# 01_ESP-CAM.net
KiCad netlist of a schematic drawn in Altium Designer
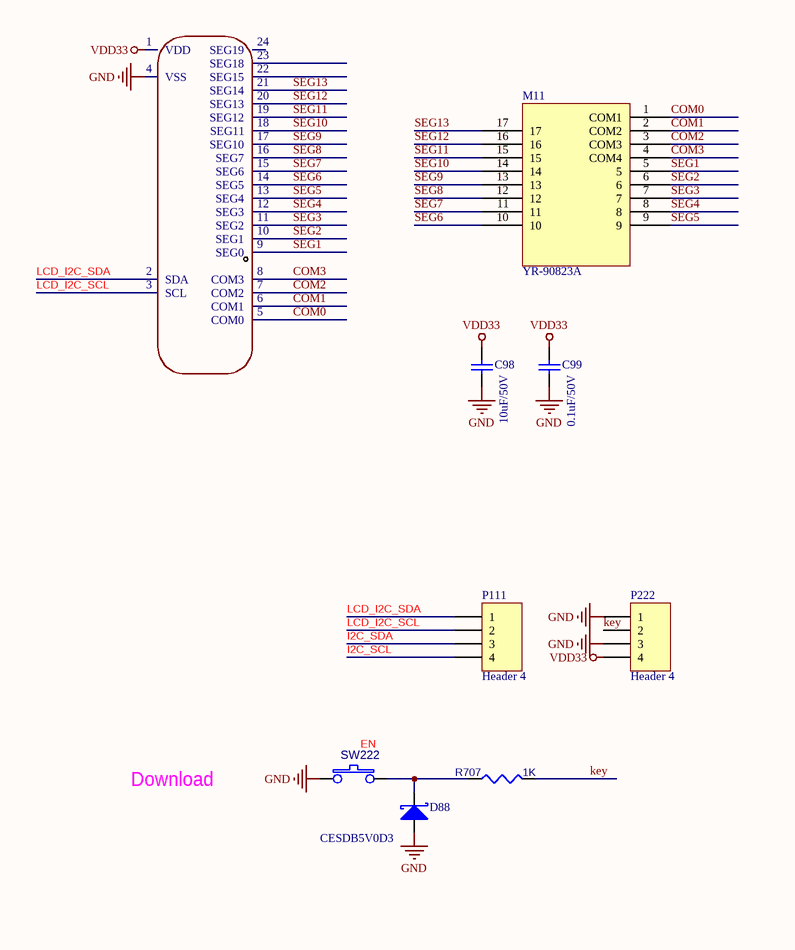
[diagram p0: 01_ESP-CAM.SchDoc, top left]
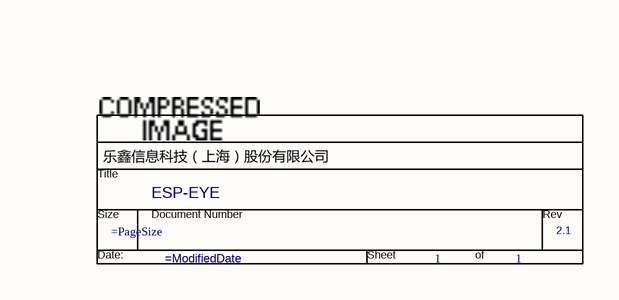
[diagram p1: 01_ESP-CAM.SchDoc, bottom right]

(export (version "E")
  (design (tool "Eeschema 10.0.6"))
  (components
    (comp (ref "*")
      (value "~")
      (fields
        (field (name "REVCODE") "2.1")
        (field (name "TITLE") "ESP-EYE")
        (field (name "PAGE NUMBER") "1")
        (field (name "PAGE COUNT") "1")
      )
      (libsource (lib "*") (part "espTitleBlock1"))
    )
    (comp (ref "C98")
      (value "10uF/50V")
      (footprint "0805C")
      (description "Capacitor")
      (fields (field (name "PUBLISHER") "Altium Limited"))
      (libsource (lib "Miscellaneous Devices") (part "Cap"))
    )
    (comp (ref "C99")
      (value "0.1uF/50V")
      (footprint "0603C")
      (description "Capacitor")
      (fields (field (name "PUBLISHER") "Altium Limited"))
      (libsource (lib "Miscellaneous Devices") (part "Cap"))
    )
    (comp (ref "D88")
      (value "CESDB5V0D3")
      (footprint "SOD323")
      (description "Schottky Diode")
      (libsource (lib "*") (part "DIODE S"))
    )
    (comp (ref "M11")
      (value "YR-90823A")
      (footprint "YR-90823A")
      (libsource (lib "Schlib_20110825") (part "YR-90823A"))
    )
    (comp (ref "P111")
      (value "Header 4")
      (footprint "1.27-4P")
      (description "Header, 4-Pin")
      (fields (field (name "PUBLISHER") "Altium Limited"))
      (libsource (lib "Miscellaneous Connectors") (part "Header 4"))
    )
    (comp (ref "P222")
      (value "Header 4")
      (footprint "1.27-4P")
      (description "Header, 4-Pin")
      (fields (field (name "PUBLISHER") "Altium Limited"))
      (libsource (lib "Miscellaneous Connectors") (part "Header 4"))
    )
    (comp (ref "R707")
      (value "1K")
      (footprint "0402R")
      (fields (field (name "Comment") "RESISTOR_0"))
      (libsource (lib "*") (part "RESISTOR_0"))
    )
    (comp (ref "SW222")
      (value "SW PUSHBUTTON")
      (footprint "SW-SMD_L3.9-W3.0-P4.45")
      (libsource (lib "*") (part "SW PUSHBUTTON"))
    )
    (comp (ref "U222")
      (value "HT16C21A-24SOP")
      (footprint "SOP65P640X265-24N")
      (fields (field (name "MANUFACTURER PART") "HT1621BM/TR"))
      (libsource (lib "Schlib_20110825") (part "HT16C21A-24SOP"))
    )
  )
  (nets
    (net (code "1") (name "/COM0") (class "Default")
      (node (ref "M11") (pin "1") (pinfunction "COM1_1") (pintype "passive"))
      (node (ref "U222") (pin "5") (pinfunction "COM0_5") (pintype "passive"))
    )
    (net (code "2") (name "/COM1") (class "Default")
      (node (ref "M11") (pin "2") (pinfunction "COM2_2") (pintype "passive"))
      (node (ref "U222") (pin "6") (pinfunction "COM1_6") (pintype "passive"))
    )
    (net (code "3") (name "/COM2") (class "Default")
      (node (ref "M11") (pin "3") (pinfunction "COM3_3") (pintype "passive"))
      (node (ref "U222") (pin "7") (pinfunction "COM2_7") (pintype "passive"))
    )
    (net (code "4") (name "/COM3") (class "Default")
      (node (ref "M11") (pin "4") (pinfunction "COM4_4") (pintype "passive"))
      (node (ref "U222") (pin "8") (pinfunction "COM3_8") (pintype "passive"))
    )
    (net (code "6") (name "/I2C_SCL") (class "Default")
      (node (ref "P111") (pin "4") (pinfunction "4_4") (pintype "passive"))
    )
    (net (code "7") (name "/I2C_SDA") (class "Default")
      (node (ref "P111") (pin "3") (pinfunction "3_3") (pintype "passive"))
    )
    (net (code "8") (name "/LCD_I2C_SCL") (class "Default")
      (node (ref "P111") (pin "2") (pinfunction "2_2") (pintype "passive"))
      (node (ref "U222") (pin "3") (pinfunction "SCL_3") (pintype "passive"))
    )
    (net (code "9") (name "/LCD_I2C_SDA") (class "Default")
      (node (ref "P111") (pin "1") (pinfunction "1_1") (pintype "passive"))
      (node (ref "U222") (pin "2") (pinfunction "SDA_2") (pintype "passive"))
    )
    (net (code "10") (name "/SEG1") (class "Default")
      (node (ref "M11") (pin "5") (pinfunction "5_5") (pintype "passive"))
      (node (ref "U222") (pin "9") (pinfunction "SEG0_9") (pintype "passive"))
    )
    (net (code "11") (name "/SEG2") (class "Default")
      (node (ref "M11") (pin "6") (pinfunction "6_6") (pintype "passive"))
      (node (ref "U222") (pin "10") (pinfunction "SEG1_10") (pintype "passive"))
    )
    (net (code "12") (name "/SEG3") (class "Default")
      (node (ref "M11") (pin "7") (pinfunction "7_7") (pintype "passive"))
      (node (ref "U222") (pin "11") (pinfunction "SEG2_11") (pintype "passive"))
    )
    (net (code "13") (name "/SEG4") (class "Default")
      (node (ref "M11") (pin "8") (pinfunction "8_8") (pintype "passive"))
      (node (ref "U222") (pin "12") (pinfunction "SEG3_12") (pintype "passive"))
    )
    (net (code "14") (name "/SEG5") (class "Default")
      (node (ref "M11") (pin "9") (pinfunction "9_9") (pintype "passive"))
      (node (ref "U222") (pin "13") (pinfunction "SEG4_13") (pintype "passive"))
    )
    (net (code "15") (name "/SEG6") (class "Default")
      (node (ref "M11") (pin "10") (pinfunction "10_10") (pintype "passive"))
      (node (ref "U222") (pin "14") (pinfunction "SEG5_14") (pintype "passive"))
    )
    (net (code "16") (name "/SEG7") (class "Default")
      (node (ref "M11") (pin "11") (pinfunction "11_11") (pintype "passive"))
      (node (ref "U222") (pin "15") (pinfunction "SEG6_15") (pintype "passive"))
    )
    (net (code "17") (name "/SEG8") (class "Default")
      (node (ref "M11") (pin "12") (pinfunction "12_12") (pintype "passive"))
      (node (ref "U222") (pin "16") (pinfunction "SEG7_16") (pintype "passive"))
    )
    (net (code "18") (name "/SEG9") (class "Default")
      (node (ref "M11") (pin "13") (pinfunction "13_13") (pintype "passive"))
      (node (ref "U222") (pin "17") (pinfunction "SEG10_17") (pintype "passive"))
    )
    (net (code "19") (name "/SEG10") (class "Default")
      (node (ref "M11") (pin "14") (pinfunction "14_14") (pintype "passive"))
      (node (ref "U222") (pin "18") (pinfunction "SEG11_18") (pintype "passive"))
    )
    (net (code "20") (name "/SEG11") (class "Default")
      (node (ref "M11") (pin "15") (pinfunction "15_15") (pintype "passive"))
      (node (ref "U222") (pin "19") (pinfunction "SEG12_19") (pintype "passive"))
    )
    (net (code "21") (name "/SEG12") (class "Default")
      (node (ref "M11") (pin "16") (pinfunction "16_16") (pintype "passive"))
      (node (ref "U222") (pin "20") (pinfunction "SEG13_20") (pintype "passive"))
    )
    (net (code "22") (name "/SEG13") (class "Default")
      (node (ref "M11") (pin "17") (pinfunction "17_17") (pintype "passive"))
      (node (ref "U222") (pin "21") (pinfunction "SEG14_21") (pintype "passive"))
    )
    (net (code "23") (name "/key") (class "Default")
      (node (ref "P222") (pin "2") (pinfunction "2_2") (pintype "passive"))
      (node (ref "R707") (pin "2") (pinfunction "2_2") (pintype "passive"))
    )
    (net (code "24") (name "GND") (class "Default")
      (node (ref "C98") (pin "1") (pinfunction "1_1") (pintype "passive"))
      (node (ref "C99") (pin "1") (pinfunction "1_1") (pintype "passive"))
      (node (ref "D88") (pin "1") (pinfunction "A_1") (pintype "passive"))
      (node (ref "P222") (pin "1") (pinfunction "1_1") (pintype "passive"))
      (node (ref "P222") (pin "3") (pinfunction "3_3") (pintype "passive"))
      (node (ref "SW222") (pin "1") (pinfunction "1_1") (pintype "passive"))
      (node (ref "U222") (pin "4") (pinfunction "VSS_4") (pintype "passive"))
    )
    (net (code "25") (name "Net-(D88-K)") (class "Default")
      (node (ref "D88") (pin "2") (pinfunction "K_2") (pintype "passive"))
      (node (ref "R707") (pin "1") (pinfunction "1_1") (pintype "passive"))
      (node (ref "SW222") (pin "2") (pinfunction "2_2") (pintype "passive"))
    )
    (net (code "26") (name "VDD33") (class "Default")
      (node (ref "C98") (pin "2") (pinfunction "2_2") (pintype "passive"))
      (node (ref "C99") (pin "2") (pinfunction "2_2") (pintype "passive"))
      (node (ref "P222") (pin "4") (pinfunction "4_4") (pintype "passive"))
      (node (ref "U222") (pin "1") (pinfunction "VDD_1") (pintype "passive"))
    )
    (net (code "27") (name "unconnected-(U222-SEG15-Pad22)") (class "Default")
      (node (ref "U222") (pin "22") (pinfunction "SEG15_22") (pintype "passive"))
    )
    (net (code "28") (name "unconnected-(U222-SEG18-Pad23)") (class "Default")
      (node (ref "U222") (pin "23") (pinfunction "SEG18_23") (pintype "passive"))
    )
    (net (code "29") (name "unconnected-(U222-SEG19-Pad24)") (class "Default")
      (node (ref "U222") (pin "24") (pinfunction "SEG19_24") (pintype "passive"))
    )
  )
)
